# HeadBoard.net
KiCad netlist of a schematic drawn in EAGLE
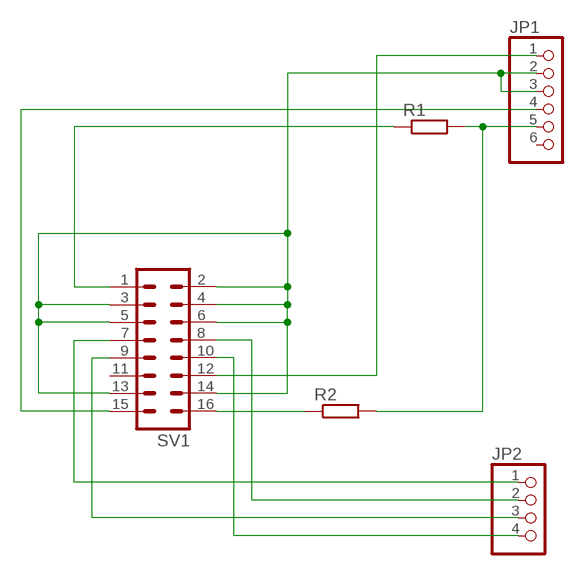
[diagram p0: schematic, sheet 1]

(export (version "E")
  (design (tool "Eeschema 10.0.6"))
  (components
    (comp (ref "JP1")
      (value "PINHD-1X6")
      (footprint "eagle-import:1X06")
      (libsource (lib "eagle-import") (part "PINHD-1X6"))
    )
    (comp (ref "JP2")
      (value "PINHD-1X4")
      (footprint "eagle-import:1X04")
      (libsource (lib "eagle-import") (part "PINHD-1X4"))
    )
    (comp (ref "R1")
      (value "R_R0805")
      (footprint "eagle-import:RESC2012X50")
      (libsource (lib "eagle-import") (part "R_R0805"))
    )
    (comp (ref "R2")
      (value "R_R0805")
      (footprint "eagle-import:RESC2012X50")
      (libsource (lib "eagle-import") (part "R_R0805"))
    )
    (comp (ref "SV1")
      (value "ML16")
      (footprint "eagle-import:ML16")
      (libsource (lib "eagle-import") (part "ML16"))
    )
  )
  (nets
    (net (code "1") (name "Net-(JP1-Pad1)") (class "Default")
      (node (ref "JP1") (pin "1") (pinfunction "1_1") (pintype "passive"))
      (node (ref "SV1") (pin "12") (pinfunction "12_12") (pintype "passive"))
    )
    (net (code "2") (name "Net-(JP1-Pad2)") (class "Default")
      (node (ref "JP1") (pin "2") (pinfunction "2_2") (pintype "passive"))
      (node (ref "JP1") (pin "3") (pinfunction "3_3") (pintype "passive"))
      (node (ref "SV1") (pin "13") (pinfunction "13_13") (pintype "passive"))
      (node (ref "SV1") (pin "14") (pinfunction "14_14") (pintype "passive"))
      (node (ref "SV1") (pin "2") (pinfunction "2_2") (pintype "passive"))
      (node (ref "SV1") (pin "3") (pinfunction "3_3") (pintype "passive"))
      (node (ref "SV1") (pin "4") (pinfunction "4_4") (pintype "passive"))
      (node (ref "SV1") (pin "5") (pinfunction "5_5") (pintype "passive"))
      (node (ref "SV1") (pin "6") (pinfunction "6_6") (pintype "passive"))
    )
    (net (code "3") (name "Net-(JP1-Pad4)") (class "Default")
      (node (ref "JP1") (pin "4") (pinfunction "4_4") (pintype "passive"))
      (node (ref "SV1") (pin "15") (pinfunction "15_15") (pintype "passive"))
    )
    (net (code "4") (name "Net-(JP1-Pad5)") (class "Default")
      (node (ref "JP1") (pin "5") (pinfunction "5_5") (pintype "passive"))
      (node (ref "R1") (pin "2") (pinfunction "2_2") (pintype "passive"))
      (node (ref "R2") (pin "2") (pinfunction "2_2") (pintype "passive"))
    )
    (net (code "5") (name "Net-(JP2-Pad1)") (class "Default")
      (node (ref "JP2") (pin "1") (pinfunction "1_1") (pintype "passive"))
      (node (ref "SV1") (pin "7") (pinfunction "7_7") (pintype "passive"))
    )
    (net (code "6") (name "Net-(JP2-Pad2)") (class "Default")
      (node (ref "JP2") (pin "2") (pinfunction "2_2") (pintype "passive"))
      (node (ref "SV1") (pin "8") (pinfunction "8_8") (pintype "passive"))
    )
    (net (code "7") (name "Net-(JP2-Pad3)") (class "Default")
      (node (ref "JP2") (pin "3") (pinfunction "3_3") (pintype "passive"))
      (node (ref "SV1") (pin "9") (pinfunction "9_9") (pintype "passive"))
    )
    (net (code "8") (name "Net-(JP2-Pad4)") (class "Default")
      (node (ref "JP2") (pin "4") (pinfunction "4_4") (pintype "passive"))
      (node (ref "SV1") (pin "10") (pinfunction "10_10") (pintype "passive"))
    )
    (net (code "9") (name "Net-(R1-Pad1)") (class "Default")
      (node (ref "R1") (pin "1") (pinfunction "1_1") (pintype "passive"))
      (node (ref "SV1") (pin "1") (pinfunction "1_1") (pintype "passive"))
    )
    (net (code "10") (name "Net-(R2-Pad1)") (class "Default")
      (node (ref "R2") (pin "1") (pinfunction "1_1") (pintype "passive"))
      (node (ref "SV1") (pin "16") (pinfunction "16_16") (pintype "passive"))
    )
    (net (code "11") (name "unconnected-(JP1-Pad6)") (class "Default")
      (node (ref "JP1") (pin "6") (pinfunction "6_6") (pintype "passive"))
    )
    (net (code "12") (name "unconnected-(SV1-Pad11)") (class "Default")
      (node (ref "SV1") (pin "11") (pinfunction "11_11") (pintype "passive"))
    )
  )
)
